# QSPI.net
KiCad netlist of a schematic drawn in Altium Designer
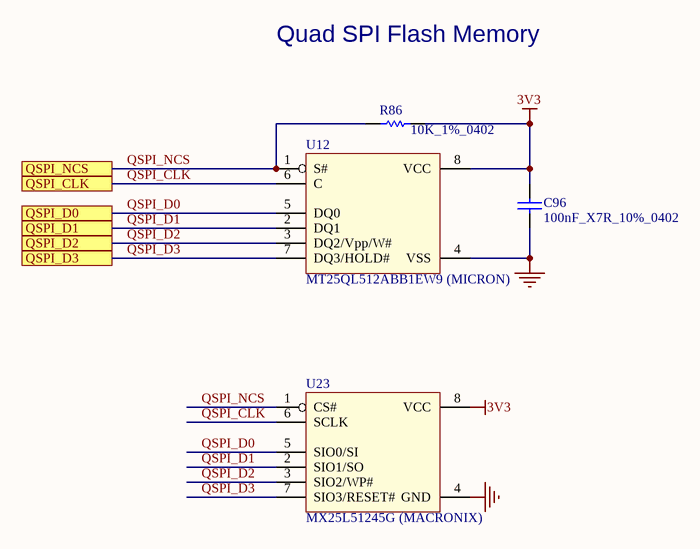
[diagram p0: QSPI.SchDoc]

(export (version "E")
  (design (tool "Eeschema 10.0.6"))
  (components
    (comp (ref "C96")
      (value "100nF_X7R_10%_0402")
      (footprint "0402C")
      (description "Capacitor,100nF,16V,X7R,10%,0402,YAGEO")
      (libsource (lib "MCD_TOOLS") (part "Cap_100nF_X7R_10%_0402"))
    )
    (comp (ref "R86")
      (value "10K_1%_0402")
      (footprint "0402R")
      (description "Resistor,10K,0402,1%,YAGEO")
      (libsource (lib "MCD_TOOLS") (part "Res_10K_1%_0402"))
    )
    (comp (ref "U12")
      (value "MT25QL512ABB1EW9 (MICRON)")
      (footprint "DFN8_1R27_6X8_TP4R8X5R16")
      (description "512Mb, 3V, Multiple I/O Serial Flash Memory, Quad/Dual")
      (libsource (lib "MCD_TOOLS_MISCELLANEOUS") (part "MT25QL512ABB1EW9"))
    )
    (comp (ref "U23")
      (value "MX25L51245G (MACRONIX)")
      (footprint "MB1225_REVB_160222_1K:SON8_1R27_6X8")
      (description "512Mb, 3V, Multiple I/O Serial Flash Memory, Quad/Dual")
      (fields (field (name "PROVIDED") "Sub Co"))
      (libsource (lib "MCD_TOOLS_MISCELLANEOUS") (part "MX25L51245G"))
    )
  )
  (nets
    (net (code "1") (name "/QSPI_CLK") (class "Default")
      (node (ref "U12") (pin "6") (pinfunction "C_6") (pintype "passive"))
      (node (ref "U23") (pin "6") (pinfunction "SCLK_6") (pintype "passive"))
    )
    (net (code "2") (name "/QSPI_D0") (class "Default")
      (node (ref "U12") (pin "5") (pinfunction "DQ0_5") (pintype "passive"))
      (node (ref "U23") (pin "5") (pinfunction "SIO0/SI_5") (pintype "passive"))
    )
    (net (code "3") (name "/QSPI_D1") (class "Default")
      (node (ref "U12") (pin "2") (pinfunction "DQ1_2") (pintype "passive"))
      (node (ref "U23") (pin "2") (pinfunction "SIO1/SO_2") (pintype "passive"))
    )
    (net (code "4") (name "/QSPI_D2") (class "Default")
      (node (ref "U12") (pin "3") (pinfunction "DQ2/Vpp/W#_3") (pintype "passive"))
      (node (ref "U23") (pin "3") (pinfunction "SIO2/WP#_3") (pintype "passive"))
    )
    (net (code "5") (name "/QSPI_D3") (class "Default")
      (node (ref "U12") (pin "7") (pinfunction "DQ3/HOLD#_7") (pintype "passive"))
      (node (ref "U23") (pin "7") (pinfunction "SIO3/RESET#_7") (pintype "passive"))
    )
    (net (code "6") (name "/QSPI_NCS") (class "Default")
      (node (ref "R86") (pin "1") (pinfunction "1_1") (pintype "passive"))
      (node (ref "U12") (pin "1") (pinfunction "S#_1") (pintype "passive"))
      (node (ref "U23") (pin "1") (pinfunction "CS#_1") (pintype "passive"))
    )
    (net (code "7") (name "3V3") (class "Default")
      (node (ref "C96") (pin "2") (pinfunction "2_2") (pintype "passive"))
      (node (ref "R86") (pin "2") (pinfunction "2_2") (pintype "passive"))
      (node (ref "U12") (pin "8") (pinfunction "VCC_8") (pintype "passive"))
      (node (ref "U23") (pin "8") (pinfunction "VCC_8") (pintype "passive"))
    )
    (net (code "8") (name "GND") (class "Default")
      (node (ref "C96") (pin "1") (pinfunction "1_1") (pintype "passive"))
      (node (ref "U12") (pin "4") (pinfunction "VSS_4") (pintype "passive"))
      (node (ref "U23") (pin "4") (pinfunction "GND_4") (pintype "passive"))
    )
  )
)
